# dyna-comp.net
KiCad netlist of a schematic drawn in EAGLE
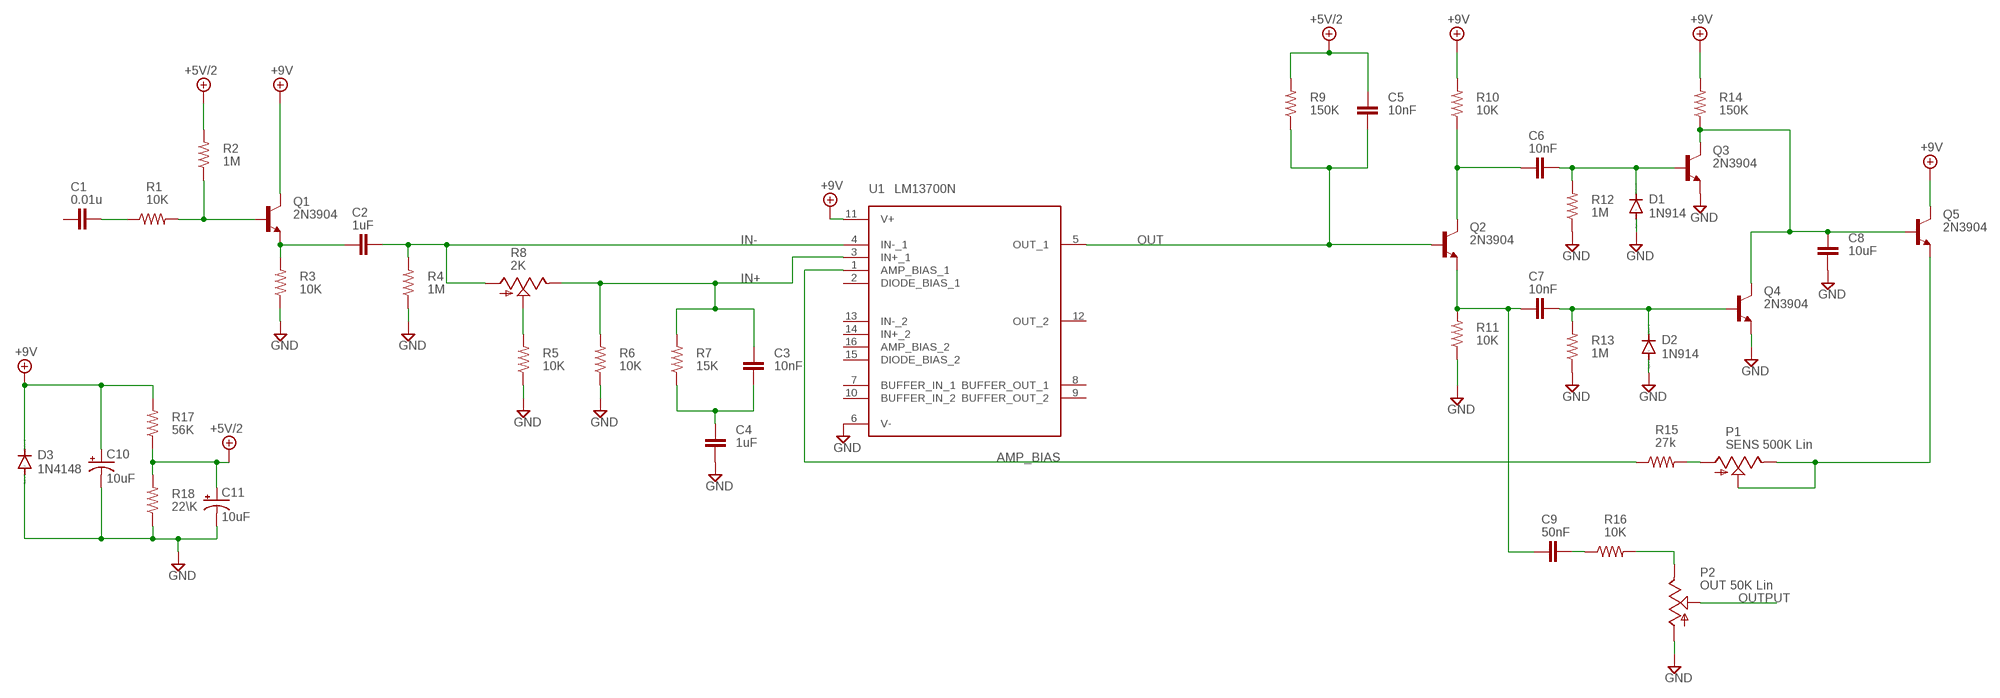
[diagram p0: schematic, sheet 1]

(export (version "E")
  (design (tool "Eeschema 10.0.6"))
  (components
    (comp (ref "C1")
      (value "0.01u")
      (footprint "eagle-import:C050-024X044")
      (libsource (lib "eagle-import") (part "C-EU050-024X044"))
    )
    (comp (ref "C2")
      (value "1uF")
      (footprint "eagle-import:C050-024X044")
      (libsource (lib "eagle-import") (part "C-EU050-024X044"))
    )
    (comp (ref "C3")
      (value "10nF")
      (footprint "eagle-import:C050-024X044")
      (libsource (lib "eagle-import") (part "C-EU050-024X044"))
    )
    (comp (ref "C4")
      (value "1uF")
      (footprint "eagle-import:C050-024X044")
      (libsource (lib "eagle-import") (part "C-EU050-024X044"))
    )
    (comp (ref "C5")
      (value "10nF")
      (footprint "eagle-import:C050-024X044")
      (libsource (lib "eagle-import") (part "C-EU050-024X044"))
    )
    (comp (ref "C6")
      (value "10nF")
      (footprint "eagle-import:C050-024X044")
      (libsource (lib "eagle-import") (part "C-EU050-024X044"))
    )
    (comp (ref "C7")
      (value "10nF")
      (footprint "eagle-import:C050-024X044")
      (libsource (lib "eagle-import") (part "C-EU050-024X044"))
    )
    (comp (ref "C8")
      (value "10uF")
      (footprint "eagle-import:C050-024X044")
      (libsource (lib "eagle-import") (part "C-EU050-024X044"))
    )
    (comp (ref "C9")
      (value "50nF")
      (footprint "eagle-import:C050-024X044")
      (libsource (lib "eagle-import") (part "C-EU050-024X044"))
    )
    (comp (ref "C10")
      (value "10uF")
      (footprint "eagle-import:TT2D5")
      (libsource (lib "eagle-import") (part "CPOL-USTT2D5"))
    )
    (comp (ref "C11")
      (value "10uF")
      (footprint "eagle-import:TT2D5")
      (libsource (lib "eagle-import") (part "CPOL-USTT2D5"))
    )
    (comp (ref "D1")
      (value "1N914")
      (footprint "eagle-import:DO35-7")
      (libsource (lib "eagle-import") (part "1N4148DO35-7"))
    )
    (comp (ref "D2")
      (value "1N914")
      (footprint "eagle-import:DO35-7")
      (libsource (lib "eagle-import") (part "1N4148DO35-7"))
    )
    (comp (ref "D3")
      (value "1N4148")
      (footprint "eagle-import:DO35-7")
      (libsource (lib "eagle-import") (part "1N4148DO35-7"))
    )
    (comp (ref "P1")
      (value "SENS 500K Lin")
      (footprint "eagle-import:POT-5.08MM")
      (libsource (lib "eagle-import") (part "POT"))
    )
    (comp (ref "P2")
      (value "OUT 50K Lin")
      (footprint "eagle-import:POT-5.08MM")
      (libsource (lib "eagle-import") (part "POT"))
    )
    (comp (ref "Q1")
      (value "2N3904")
      (footprint "eagle-import:TO92")
      (libsource (lib "eagle-import") (part "-NPN-TO92"))
    )
    (comp (ref "Q2")
      (value "2N3904")
      (footprint "eagle-import:TO92")
      (libsource (lib "eagle-import") (part "-NPN-TO92"))
    )
    (comp (ref "Q3")
      (value "2N3904")
      (footprint "eagle-import:TO92")
      (libsource (lib "eagle-import") (part "-NPN-TO92"))
    )
    (comp (ref "Q4")
      (value "2N3904")
      (footprint "eagle-import:TO92")
      (libsource (lib "eagle-import") (part "-NPN-TO92"))
    )
    (comp (ref "Q5")
      (value "2N3904")
      (footprint "eagle-import:TO92")
      (libsource (lib "eagle-import") (part "-NPN-TO92"))
    )
    (comp (ref "R1")
      (value "10K")
      (footprint "eagle-import:0309_12")
      (libsource (lib "eagle-import") (part "R-US_0309/12"))
    )
    (comp (ref "R2")
      (value "1M")
      (footprint "eagle-import:0309_12")
      (libsource (lib "eagle-import") (part "R-US_0309/12"))
    )
    (comp (ref "R3")
      (value "10K")
      (footprint "eagle-import:0309_12")
      (libsource (lib "eagle-import") (part "R-US_0309/12"))
    )
    (comp (ref "R4")
      (value "1M")
      (footprint "eagle-import:0309_12")
      (libsource (lib "eagle-import") (part "R-US_0309/12"))
    )
    (comp (ref "R5")
      (value "10K")
      (footprint "eagle-import:0309_12")
      (libsource (lib "eagle-import") (part "R-US_0309/12"))
    )
    (comp (ref "R6")
      (value "10K")
      (footprint "eagle-import:0309_12")
      (libsource (lib "eagle-import") (part "R-US_0309/12"))
    )
    (comp (ref "R7")
      (value "15K")
      (footprint "eagle-import:0309_12")
      (libsource (lib "eagle-import") (part "R-US_0309/12"))
    )
    (comp (ref "R8")
      (value "2K")
      (footprint "eagle-import:CA6V")
      (libsource (lib "eagle-import") (part "TRIM_US-CA6V"))
    )
    (comp (ref "R9")
      (value "150K")
      (footprint "eagle-import:0309_12")
      (libsource (lib "eagle-import") (part "R-US_0309/12"))
    )
    (comp (ref "R10")
      (value "10K")
      (footprint "eagle-import:0309_12")
      (libsource (lib "eagle-import") (part "R-US_0309/12"))
    )
    (comp (ref "R11")
      (value "10K")
      (footprint "eagle-import:0309_12")
      (libsource (lib "eagle-import") (part "R-US_0309/12"))
    )
    (comp (ref "R12")
      (value "1M")
      (footprint "eagle-import:0309_12")
      (libsource (lib "eagle-import") (part "R-US_0309/12"))
    )
    (comp (ref "R13")
      (value "1M")
      (footprint "eagle-import:0309_12")
      (libsource (lib "eagle-import") (part "R-US_0309/12"))
    )
    (comp (ref "R14")
      (value "150K")
      (footprint "eagle-import:0309_12")
      (libsource (lib "eagle-import") (part "R-US_0309/12"))
    )
    (comp (ref "R15")
      (value "27k")
      (footprint "eagle-import:0309_12")
      (libsource (lib "eagle-import") (part "R-US_0309/12"))
    )
    (comp (ref "R16")
      (value "10K")
      (footprint "eagle-import:0309_12")
      (libsource (lib "eagle-import") (part "R-US_0309/12"))
    )
    (comp (ref "R17")
      (value "56K")
      (footprint "eagle-import:0309_12")
      (libsource (lib "eagle-import") (part "R-US_0309/12"))
    )
    (comp (ref "R18")
      (value "22\\K")
      (footprint "eagle-import:0309_12")
      (libsource (lib "eagle-import") (part "R-US_0309/12"))
    )
    (comp (ref "U1")
      (value "LM13700N")
      (footprint "eagle-import:DIL16")
      (libsource (lib "eagle-import") (part "LM13700N"))
    )
  )
  (nets
    (net (code "1") (name "+5V{slash}2") (class "Default")
      (node (ref "C11") (pin "+") (pinfunction "+_+") (pintype "passive"))
      (node (ref "C5") (pin "1") (pinfunction "1_1") (pintype "passive"))
      (node (ref "R17") (pin "1") (pinfunction "1_1") (pintype "passive"))
      (node (ref "R18") (pin "2") (pinfunction "2_2") (pintype "passive"))
      (node (ref "R2") (pin "2") (pinfunction "2_2") (pintype "passive"))
      (node (ref "R9") (pin "2") (pinfunction "2_2") (pintype "passive"))
    )
    (net (code "2") (name "+9V") (class "Default")
      (node (ref "C10") (pin "+") (pinfunction "+_+") (pintype "passive"))
      (node (ref "D3") (pin "C") (pinfunction "C_C") (pintype "passive"))
      (node (ref "Q1") (pin "3") (pinfunction "C_3") (pintype "passive"))
      (node (ref "Q5") (pin "3") (pinfunction "C_3") (pintype "passive"))
      (node (ref "R10") (pin "2") (pinfunction "2_2") (pintype "passive"))
      (node (ref "R14") (pin "2") (pinfunction "2_2") (pintype "passive"))
      (node (ref "R17") (pin "2") (pinfunction "2_2") (pintype "passive"))
      (node (ref "U1") (pin "11") (pinfunction "V+_11") (pintype "bidirectional"))
    )
    (net (code "3") (name "/AMP_BIAS") (class "Default")
      (node (ref "R15") (pin "1") (pinfunction "1_1") (pintype "passive"))
      (node (ref "U1") (pin "1") (pinfunction "AMP_BIAS_1_1") (pintype "bidirectional"))
    )
    (net (code "4") (name "/IN+") (class "Default")
      (node (ref "C3") (pin "1") (pinfunction "1_1") (pintype "passive"))
      (node (ref "R6") (pin "2") (pinfunction "2_2") (pintype "passive"))
      (node (ref "R7") (pin "2") (pinfunction "2_2") (pintype "passive"))
      (node (ref "R8") (pin "E") (pinfunction "E_E") (pintype "passive"))
      (node (ref "U1") (pin "3") (pinfunction "IN+_1_3") (pintype "bidirectional"))
    )
    (net (code "5") (name "/IN-") (class "Default")
      (node (ref "C2") (pin "2") (pinfunction "2_2") (pintype "passive"))
      (node (ref "R4") (pin "2") (pinfunction "2_2") (pintype "passive"))
      (node (ref "R8") (pin "A") (pinfunction "A_A") (pintype "passive"))
      (node (ref "U1") (pin "4") (pinfunction "IN-_1_4") (pintype "bidirectional"))
    )
    (net (code "6") (name "/OUT") (class "Default")
      (node (ref "C5") (pin "2") (pinfunction "2_2") (pintype "passive"))
      (node (ref "Q2") (pin "2") (pinfunction "B_2") (pintype "passive"))
      (node (ref "R9") (pin "1") (pinfunction "1_1") (pintype "passive"))
      (node (ref "U1") (pin "5") (pinfunction "OUT_1_5") (pintype "bidirectional"))
    )
    (net (code "7") (name "/OUTPUT") (class "Default")
      (node (ref "P2") (pin "2") (pinfunction "2_2") (pintype "passive"))
    )
    (net (code "8") (name "GND") (class "Default")
      (node (ref "C10") (pin "-") (pinfunction "-_-") (pintype "passive"))
      (node (ref "C11") (pin "-") (pinfunction "-_-") (pintype "passive"))
      (node (ref "C4") (pin "2") (pinfunction "2_2") (pintype "passive"))
      (node (ref "C8") (pin "2") (pinfunction "2_2") (pintype "passive"))
      (node (ref "D1") (pin "A") (pinfunction "A_A") (pintype "passive"))
      (node (ref "D2") (pin "A") (pinfunction "A_A") (pintype "passive"))
      (node (ref "D3") (pin "A") (pinfunction "A_A") (pintype "passive"))
      (node (ref "P2") (pin "1") (pinfunction "1_1") (pintype "passive"))
      (node (ref "Q3") (pin "1") (pinfunction "E_1") (pintype "passive"))
      (node (ref "Q4") (pin "1") (pinfunction "E_1") (pintype "passive"))
      (node (ref "R11") (pin "1") (pinfunction "1_1") (pintype "passive"))
      (node (ref "R12") (pin "1") (pinfunction "1_1") (pintype "passive"))
      (node (ref "R13") (pin "1") (pinfunction "1_1") (pintype "passive"))
      (node (ref "R18") (pin "1") (pinfunction "1_1") (pintype "passive"))
      (node (ref "R3") (pin "1") (pinfunction "1_1") (pintype "passive"))
      (node (ref "R4") (pin "1") (pinfunction "1_1") (pintype "passive"))
      (node (ref "R5") (pin "1") (pinfunction "1_1") (pintype "passive"))
      (node (ref "R6") (pin "1") (pinfunction "1_1") (pintype "passive"))
      (node (ref "U1") (pin "6") (pinfunction "V-_6") (pintype "bidirectional"))
    )
    (net (code "9") (name "Net-(C1-Pad2)") (class "Default")
      (node (ref "C1") (pin "2") (pinfunction "2_2") (pintype "passive"))
      (node (ref "R1") (pin "1") (pinfunction "1_1") (pintype "passive"))
    )
    (net (code "10") (name "Net-(C3-Pad2)") (class "Default")
      (node (ref "C3") (pin "2") (pinfunction "2_2") (pintype "passive"))
      (node (ref "C4") (pin "1") (pinfunction "1_1") (pintype "passive"))
      (node (ref "R7") (pin "1") (pinfunction "1_1") (pintype "passive"))
    )
    (net (code "11") (name "Net-(C9-Pad2)") (class "Default")
      (node (ref "C9") (pin "2") (pinfunction "2_2") (pintype "passive"))
      (node (ref "R16") (pin "1") (pinfunction "1_1") (pintype "passive"))
    )
    (net (code "12") (name "Net-(P1-Pad1)") (class "Default")
      (node (ref "P1") (pin "1") (pinfunction "1_1") (pintype "passive"))
      (node (ref "R15") (pin "2") (pinfunction "2_2") (pintype "passive"))
    )
    (net (code "13") (name "Net-(P2-Pad3)") (class "Default")
      (node (ref "P2") (pin "3") (pinfunction "3_3") (pintype "passive"))
      (node (ref "R16") (pin "2") (pinfunction "2_2") (pintype "passive"))
    )
    (net (code "14") (name "Net-(Q1-B)") (class "Default")
      (node (ref "Q1") (pin "2") (pinfunction "B_2") (pintype "passive"))
      (node (ref "R1") (pin "2") (pinfunction "2_2") (pintype "passive"))
      (node (ref "R2") (pin "1") (pinfunction "1_1") (pintype "passive"))
    )
    (net (code "15") (name "Net-(Q1-E)") (class "Default")
      (node (ref "C2") (pin "1") (pinfunction "1_1") (pintype "passive"))
      (node (ref "Q1") (pin "1") (pinfunction "E_1") (pintype "passive"))
      (node (ref "R3") (pin "2") (pinfunction "2_2") (pintype "passive"))
    )
    (net (code "16") (name "Net-(Q2-C)") (class "Default")
      (node (ref "C6") (pin "1") (pinfunction "1_1") (pintype "passive"))
      (node (ref "Q2") (pin "3") (pinfunction "C_3") (pintype "passive"))
      (node (ref "R10") (pin "1") (pinfunction "1_1") (pintype "passive"))
    )
    (net (code "17") (name "Net-(Q2-E)") (class "Default")
      (node (ref "C7") (pin "1") (pinfunction "1_1") (pintype "passive"))
      (node (ref "C9") (pin "1") (pinfunction "1_1") (pintype "passive"))
      (node (ref "Q2") (pin "1") (pinfunction "E_1") (pintype "passive"))
      (node (ref "R11") (pin "2") (pinfunction "2_2") (pintype "passive"))
    )
    (net (code "18") (name "Net-(Q3-B)") (class "Default")
      (node (ref "C6") (pin "2") (pinfunction "2_2") (pintype "passive"))
      (node (ref "D1") (pin "C") (pinfunction "C_C") (pintype "passive"))
      (node (ref "Q3") (pin "2") (pinfunction "B_2") (pintype "passive"))
      (node (ref "R12") (pin "2") (pinfunction "2_2") (pintype "passive"))
    )
    (net (code "19") (name "Net-(Q3-C)") (class "Default")
      (node (ref "C8") (pin "1") (pinfunction "1_1") (pintype "passive"))
      (node (ref "Q3") (pin "3") (pinfunction "C_3") (pintype "passive"))
      (node (ref "Q4") (pin "3") (pinfunction "C_3") (pintype "passive"))
      (node (ref "Q5") (pin "2") (pinfunction "B_2") (pintype "passive"))
      (node (ref "R14") (pin "1") (pinfunction "1_1") (pintype "passive"))
    )
    (net (code "20") (name "Net-(Q4-B)") (class "Default")
      (node (ref "C7") (pin "2") (pinfunction "2_2") (pintype "passive"))
      (node (ref "D2") (pin "C") (pinfunction "C_C") (pintype "passive"))
      (node (ref "Q4") (pin "2") (pinfunction "B_2") (pintype "passive"))
      (node (ref "R13") (pin "2") (pinfunction "2_2") (pintype "passive"))
    )
    (net (code "21") (name "Net-(Q5-E)") (class "Default")
      (node (ref "P1") (pin "2") (pinfunction "2_2") (pintype "passive"))
      (node (ref "P1") (pin "3") (pinfunction "3_3") (pintype "passive"))
      (node (ref "Q5") (pin "1") (pinfunction "E_1") (pintype "passive"))
    )
    (net (code "22") (name "Net-(R5-Pad2)") (class "Default")
      (node (ref "R5") (pin "2") (pinfunction "2_2") (pintype "passive"))
      (node (ref "R8") (pin "S") (pinfunction "S_S") (pintype "passive"))
    )
    (net (code "23") (name "unconnected-(C1-Pad1)") (class "Default")
      (node (ref "C1") (pin "1") (pinfunction "1_1") (pintype "passive"))
    )
    (net (code "24") (name "unconnected-(U1-AMP_BIAS_2-Pad16)") (class "Default")
      (node (ref "U1") (pin "16") (pinfunction "AMP_BIAS_2_16") (pintype "bidirectional"))
    )
    (net (code "25") (name "unconnected-(U1-BUFFER_IN_1-Pad7)") (class "Default")
      (node (ref "U1") (pin "7") (pinfunction "BUFFER_IN_1_7") (pintype "bidirectional"))
    )
    (net (code "26") (name "unconnected-(U1-BUFFER_IN_2-Pad10)") (class "Default")
      (node (ref "U1") (pin "10") (pinfunction "BUFFER_IN_2_10") (pintype "bidirectional"))
    )
    (net (code "27") (name "unconnected-(U1-BUFFER_OUT_1-Pad8)") (class "Default")
      (node (ref "U1") (pin "8") (pinfunction "BUFFER_OUT_1_8") (pintype "bidirectional"))
    )
    (net (code "28") (name "unconnected-(U1-BUFFER_OUT_2-Pad9)") (class "Default")
      (node (ref "U1") (pin "9") (pinfunction "BUFFER_OUT_2_9") (pintype "bidirectional"))
    )
    (net (code "29") (name "unconnected-(U1-DIODE_BIAS_1-Pad2)") (class "Default")
      (node (ref "U1") (pin "2") (pinfunction "DIODE_BIAS_1_2") (pintype "bidirectional"))
    )
    (net (code "30") (name "unconnected-(U1-DIODE_BIAS_2-Pad15)") (class "Default")
      (node (ref "U1") (pin "15") (pinfunction "DIODE_BIAS_2_15") (pintype "bidirectional"))
    )
    (net (code "31") (name "unconnected-(U1-IN+_2-Pad14)") (class "Default")
      (node (ref "U1") (pin "14") (pinfunction "IN+_2_14") (pintype "bidirectional"))
    )
    (net (code "32") (name "unconnected-(U1-IN-_2-Pad13)") (class "Default")
      (node (ref "U1") (pin "13") (pinfunction "IN-_2_13") (pintype "bidirectional"))
    )
    (net (code "33") (name "unconnected-(U1-OUT_2-Pad12)") (class "Default")
      (node (ref "U1") (pin "12") (pinfunction "OUT_2_12") (pintype "bidirectional"))
    )
  )
)
